# JBC_Station_V3.net
KiCad netlist of a schematic drawn in EAGLE
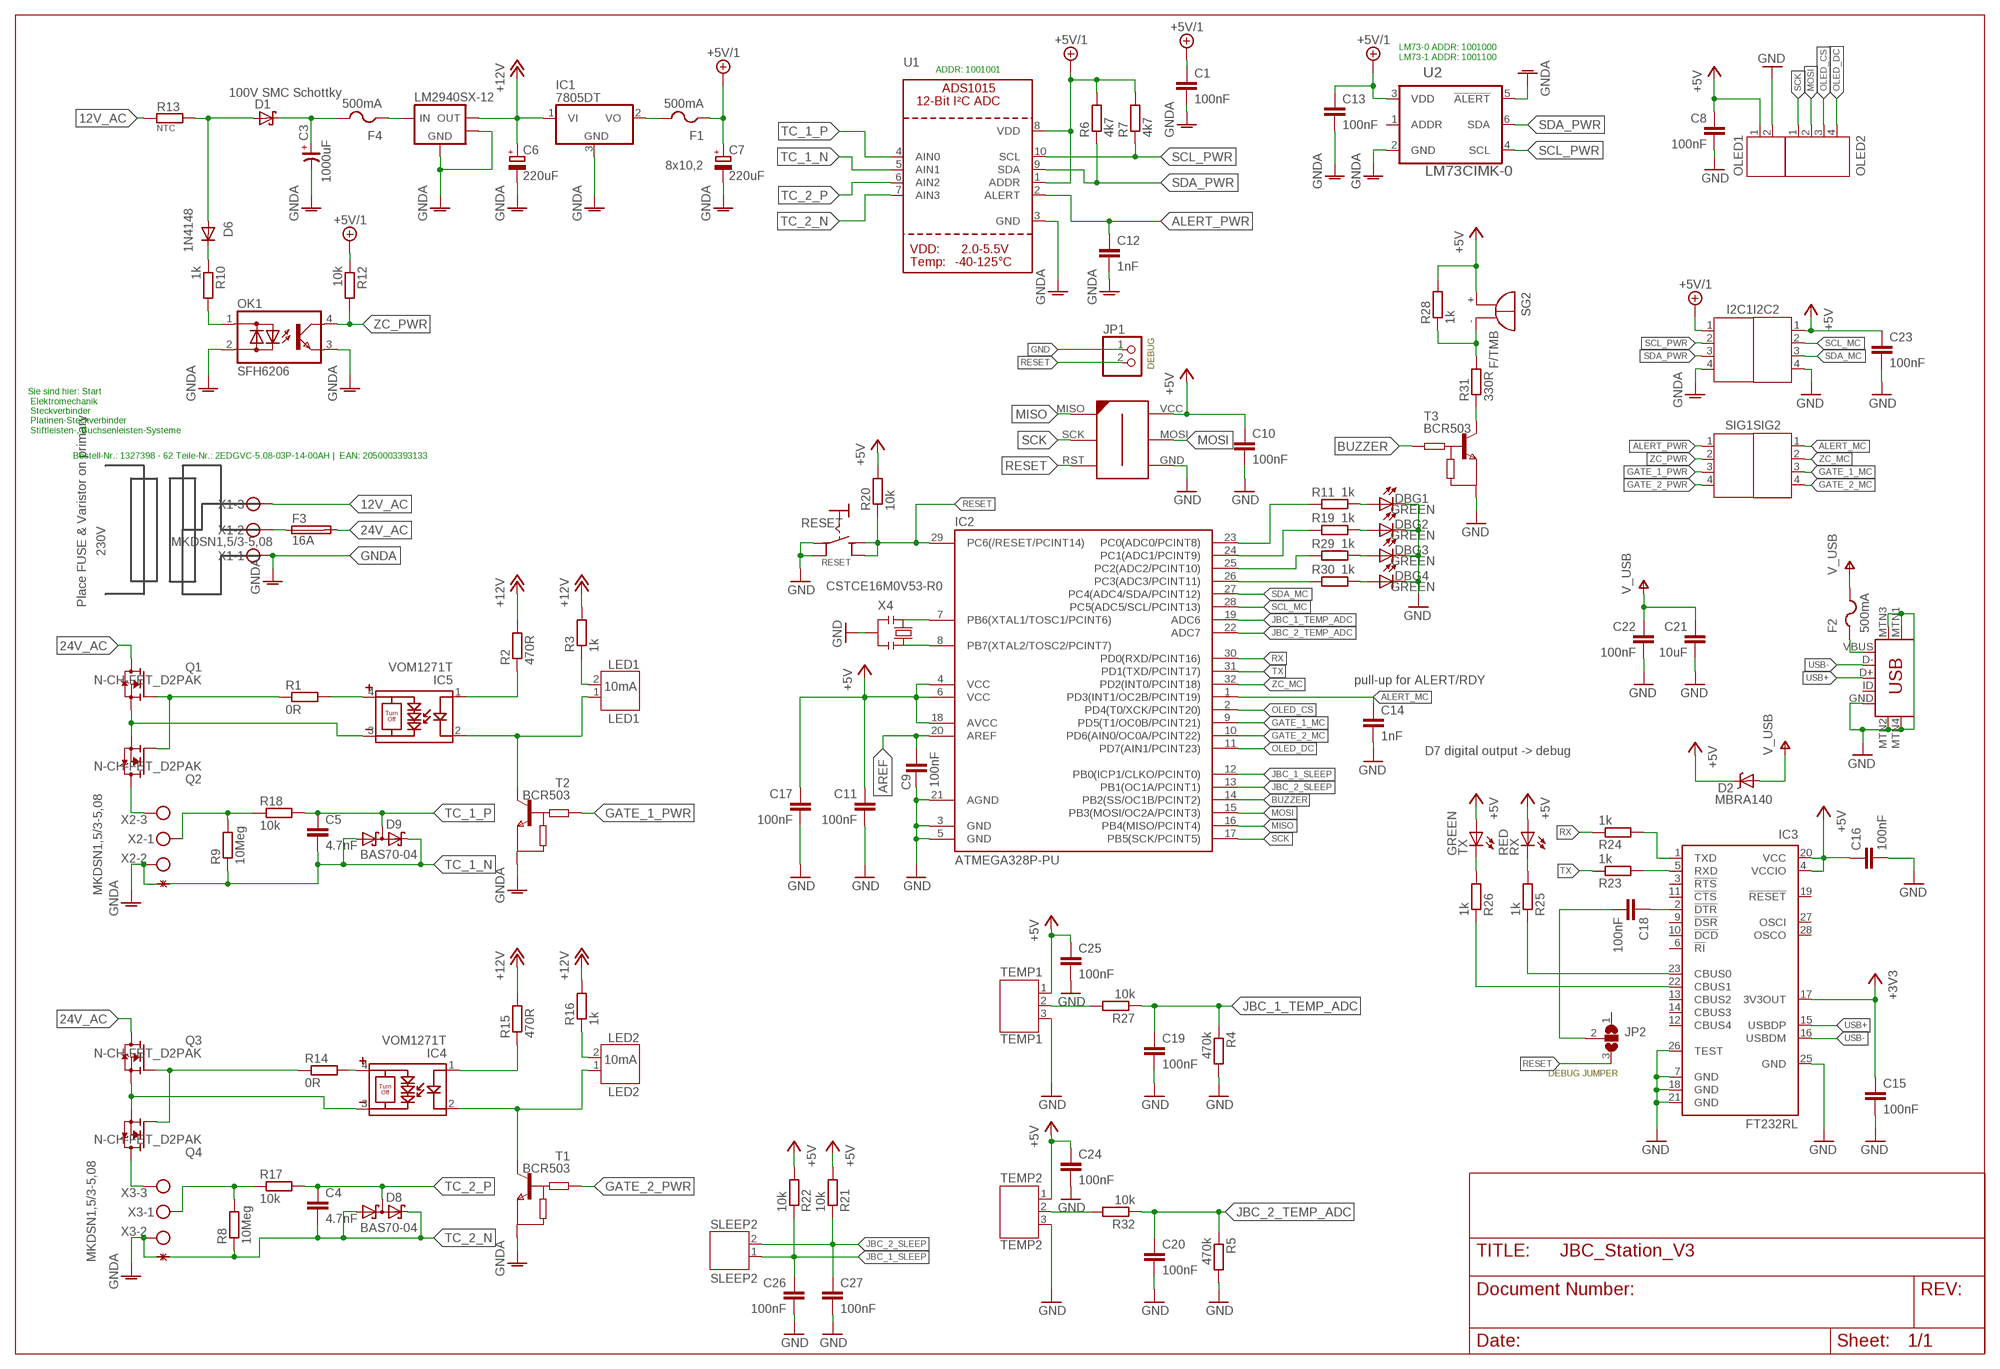
[diagram p0: schematic, sheet 1]

(export (version "E")
  (design (tool "Eeschema 10.0.6"))
  (components
    (comp (ref "C1")
      (value "100nF")
      (footprint "eagle-import:C0805")
      (libsource (lib "eagle-import") (part "C-EUC0805"))
    )
    (comp (ref "C3")
      (value "1000uF")
      (footprint "eagle-import:CSV-H")
      (libsource (lib "eagle-import") (part "CP_SV-H"))
    )
    (comp (ref "C4")
      (value "4.7nF")
      (footprint "eagle-import:C0805")
      (libsource (lib "eagle-import") (part "C-EUC0805"))
    )
    (comp (ref "C5")
      (value "4.7nF")
      (footprint "eagle-import:C0805")
      (libsource (lib "eagle-import") (part "C-EUC0805"))
    )
    (comp (ref "C6")
      (value "220uF")
      (footprint "eagle-import:PANASONIC_E")
      (libsource (lib "eagle-import") (part "CPOL-EUE"))
    )
    (comp (ref "C7")
      (value "220uF")
      (footprint "eagle-import:PANASONIC_E")
      (libsource (lib "eagle-import") (part "CPOL-EUE"))
    )
    (comp (ref "C8")
      (value "100nF")
      (footprint "eagle-import:C0805")
      (libsource (lib "eagle-import") (part "C-EUC0805"))
    )
    (comp (ref "C9")
      (value "100nF")
      (footprint "eagle-import:C0805")
      (libsource (lib "eagle-import") (part "C-EUC0805"))
    )
    (comp (ref "C10")
      (value "100nF")
      (footprint "eagle-import:C0805")
      (libsource (lib "eagle-import") (part "C-EUC0805"))
    )
    (comp (ref "C11")
      (value "100nF")
      (footprint "eagle-import:C0805")
      (libsource (lib "eagle-import") (part "C-EUC0805"))
    )
    (comp (ref "C12")
      (value "1nF")
      (footprint "eagle-import:C0805")
      (libsource (lib "eagle-import") (part "C-EUC0805"))
    )
    (comp (ref "C13")
      (value "100nF")
      (footprint "eagle-import:C0805")
      (libsource (lib "eagle-import") (part "C-EUC0805"))
    )
    (comp (ref "C14")
      (value "1nF")
      (footprint "eagle-import:C0805")
      (libsource (lib "eagle-import") (part "C-EUC0805"))
    )
    (comp (ref "C15")
      (value "100nF")
      (footprint "eagle-import:C0805")
      (libsource (lib "eagle-import") (part "C-EUC0805"))
    )
    (comp (ref "C16")
      (value "100nF")
      (footprint "eagle-import:C0805")
      (libsource (lib "eagle-import") (part "C-EUC0805"))
    )
    (comp (ref "C17")
      (value "100nF")
      (footprint "eagle-import:C0805")
      (libsource (lib "eagle-import") (part "C-EUC0805"))
    )
    (comp (ref "C18")
      (value "100nF")
      (footprint "eagle-import:C0805")
      (libsource (lib "eagle-import") (part "C-EUC0805"))
    )
    (comp (ref "C19")
      (value "100nF")
      (footprint "eagle-import:C0805")
      (libsource (lib "eagle-import") (part "C-EUC0805"))
    )
    (comp (ref "C20")
      (value "100nF")
      (footprint "eagle-import:C0805")
      (libsource (lib "eagle-import") (part "C-EUC0805"))
    )
    (comp (ref "C21")
      (value "10uF")
      (footprint "eagle-import:C1210")
      (libsource (lib "eagle-import") (part "C-EUC1210"))
    )
    (comp (ref "C22")
      (value "100nF")
      (footprint "eagle-import:C0805")
      (libsource (lib "eagle-import") (part "C-EUC0805"))
    )
    (comp (ref "C23")
      (value "100nF")
      (footprint "eagle-import:C0805")
      (libsource (lib "eagle-import") (part "C-EUC0805"))
    )
    (comp (ref "C24")
      (value "100nF")
      (footprint "eagle-import:C0805")
      (libsource (lib "eagle-import") (part "C-EUC0805"))
    )
    (comp (ref "C25")
      (value "100nF")
      (footprint "eagle-import:C0805")
      (libsource (lib "eagle-import") (part "C-EUC0805"))
    )
    (comp (ref "C26")
      (value "100nF")
      (footprint "eagle-import:C0805")
      (libsource (lib "eagle-import") (part "C-EUC0805"))
    )
    (comp (ref "C27")
      (value "100nF")
      (footprint "eagle-import:C0805")
      (libsource (lib "eagle-import") (part "C-EUC0805"))
    )
    (comp (ref "D1")
      (value "100V SMC Schottky")
      (footprint "eagle-import:SMC")
      (libsource (lib "eagle-import") (part "SCHOTTKY-DIODESMC"))
    )
    (comp (ref "D2")
      (value "MBRA140")
      (footprint "eagle-import:SMA-DIODE")
      (libsource (lib "eagle-import") (part "DIODE-SCHOTTKY_"))
    )
    (comp (ref "D6")
      (value "1N4148")
      (footprint "eagle-import:MINIMELF")
      (libsource (lib "eagle-import") (part "DIODE-MINIMELF"))
    )
    (comp (ref "D8")
      (value "BAS70-04")
      (footprint "eagle-import:SOT23")
      (libsource (lib "eagle-import") (part "BAS70-04"))
    )
    (comp (ref "D9")
      (value "BAS70-04")
      (footprint "eagle-import:SOT23")
      (libsource (lib "eagle-import") (part "BAS70-04"))
    )
    (comp (ref "DBG1")
      (value "GREEN")
      (footprint "eagle-import:CHIP-LED0603")
      (libsource (lib "eagle-import") (part "LEDCHIP-LED0603"))
    )
    (comp (ref "DBG2")
      (value "GREEN")
      (footprint "eagle-import:CHIP-LED0603")
      (libsource (lib "eagle-import") (part "LEDCHIP-LED0603"))
    )
    (comp (ref "DBG3")
      (value "GREEN")
      (footprint "eagle-import:CHIP-LED0603")
      (libsource (lib "eagle-import") (part "LEDCHIP-LED0603"))
    )
    (comp (ref "DBG4")
      (value "GREEN")
      (footprint "eagle-import:CHIP-LED0603")
      (libsource (lib "eagle-import") (part "LEDCHIP-LED0603"))
    )
    (comp (ref "F1")
      (value "500mA")
      (footprint "eagle-import:R1206")
      (libsource (lib "eagle-import") (part "PTCFUSE-1206"))
    )
    (comp (ref "F2")
      (value "500mA")
      (footprint "eagle-import:R1206")
      (libsource (lib "eagle-import") (part "PTCFUSE-1206"))
    )
    (comp (ref "F3")
      (value "16A")
      (footprint "eagle-import:SH25")
      (fields (field (name "MF") "SCHURTER") (field (name "MPN") "0031.8211"))
      (libsource (lib "eagle-import") (part "SH25"))
    )
    (comp (ref "F4")
      (value "500mA")
      (footprint "eagle-import:R1206")
      (libsource (lib "eagle-import") (part "PTCFUSE-1206"))
    )
    (comp (ref "I2C1")
      (value "JST-PH4")
      (footprint "eagle-import:JST-PH4")
      (libsource (lib "eagle-import") (part "JST-PH4"))
    )
    (comp (ref "I2C2")
      (value "JST-PH4")
      (footprint "eagle-import:JST-PH4")
      (libsource (lib "eagle-import") (part "JST-PH4"))
    )
    (comp (ref "IC1")
      (value "7805DT")
      (footprint "eagle-import:TO252")
      (libsource (lib "eagle-import") (part "78DT05"))
    )
    (comp (ref "IC2")
      (value "ATMEGA328P-PU")
      (footprint "eagle-import:TQFP32-08")
      (libsource (lib "eagle-import") (part "MEGA48/88/168-AU"))
    )
    (comp (ref "IC3")
      (value "FT232RL")
      (footprint "eagle-import:SSOP28")
      (libsource (lib "eagle-import") (part "FT232RL"))
    )
    (comp (ref "IC4")
      (value "VOM1271T")
      (footprint "eagle-import:SOP-4")
      (libsource (lib "eagle-import") (part "VOM1271T"))
    )
    (comp (ref "IC5")
      (value "VOM1271T")
      (footprint "eagle-import:SOP-4")
      (libsource (lib "eagle-import") (part "VOM1271T"))
    )
    (comp (ref "JP1")
      (value "PINHD-1X2_2.54")
      (footprint "eagle-import:1X02")
      (libsource (lib "eagle-import") (part "PINHD-1X2_2.54"))
    )
    (comp (ref "JP2")
      (value "SJ2W")
      (footprint "eagle-import:SJ_2")
      (libsource (lib "eagle-import") (part "SJ2W"))
    )
    (comp (ref "LED1")
      (value "LED1")
      (footprint "eagle-import:JST-PH2")
      (libsource (lib "eagle-import") (part "JST-PH2"))
    )
    (comp (ref "LED2")
      (value "LED2")
      (footprint "eagle-import:JST-PH2")
      (libsource (lib "eagle-import") (part "JST-PH2"))
    )
    (comp (ref "LM2940SX-12")
      (value "LM2940KTT")
      (footprint "eagle-import:TO263-3")
      (libsource (lib "eagle-import") (part "LM2940KTT"))
    )
    (comp (ref "OK1")
      (value "SFH6206")
      (footprint "eagle-import:DIL4-SMD")
      (fields (field (name "MF") "VISHAY/TELEFUNKEN") (field (name "MPN") "SFH6206-3"))
      (libsource (lib "eagle-import") (part "SFH6206"))
    )
    (comp (ref "OLED1")
      (value "JST-PH2")
      (footprint "eagle-import:JST-PH2")
      (libsource (lib "eagle-import") (part "JST-PH2"))
    )
    (comp (ref "OLED2")
      (value "JST-PH4")
      (footprint "eagle-import:JST-PH4")
      (libsource (lib "eagle-import") (part "JST-PH4"))
    )
    (comp (ref "Q1")
      (value "N-CH-FET_D2PAK")
      (footprint "eagle-import:D2PACK")
      (libsource (lib "eagle-import") (part "N-CH-FET_D2PAK"))
    )
    (comp (ref "Q2")
      (value "N-CH-FET_D2PAK")
      (footprint "eagle-import:D2PACK")
      (libsource (lib "eagle-import") (part "N-CH-FET_D2PAK"))
    )
    (comp (ref "Q3")
      (value "N-CH-FET_D2PAK")
      (footprint "eagle-import:D2PACK")
      (libsource (lib "eagle-import") (part "N-CH-FET_D2PAK"))
    )
    (comp (ref "Q4")
      (value "N-CH-FET_D2PAK")
      (footprint "eagle-import:D2PACK")
      (libsource (lib "eagle-import") (part "N-CH-FET_D2PAK"))
    )
    (comp (ref "R1")
      (value "0R")
      (footprint "eagle-import:R0805")
      (libsource (lib "eagle-import") (part "R-EU_R0805"))
    )
    (comp (ref "R2")
      (value "470R")
      (footprint "eagle-import:R0805")
      (libsource (lib "eagle-import") (part "R-EU_R0805"))
    )
    (comp (ref "R3")
      (value "1k")
      (footprint "eagle-import:R0805")
      (libsource (lib "eagle-import") (part "R-EU_R0805"))
    )
    (comp (ref "R4")
      (value "470k")
      (footprint "eagle-import:R0805")
      (libsource (lib "eagle-import") (part "R-EU_R0805"))
    )
    (comp (ref "R5")
      (value "470k")
      (footprint "eagle-import:R0805")
      (libsource (lib "eagle-import") (part "R-EU_R0805"))
    )
    (comp (ref "R6")
      (value "4k7")
      (footprint "eagle-import:R0805")
      (libsource (lib "eagle-import") (part "R-EU_R0805"))
    )
    (comp (ref "R7")
      (value "4k7")
      (footprint "eagle-import:R0805")
      (libsource (lib "eagle-import") (part "R-EU_R0805"))
    )
    (comp (ref "R8")
      (value "10Meg")
      (footprint "eagle-import:R0805")
      (libsource (lib "eagle-import") (part "R-EU_R0805"))
    )
    (comp (ref "R9")
      (value "10Meg")
      (footprint "eagle-import:R0805")
      (libsource (lib "eagle-import") (part "R-EU_R0805"))
    )
    (comp (ref "R10")
      (value "1k")
      (footprint "eagle-import:R0805")
      (libsource (lib "eagle-import") (part "R-EU_R0805"))
    )
    (comp (ref "R11")
      (value "1k")
      (footprint "eagle-import:R0805")
      (libsource (lib "eagle-import") (part "R-EU_R0805"))
    )
    (comp (ref "R12")
      (value "10k")
      (footprint "eagle-import:R0805")
      (libsource (lib "eagle-import") (part "R-EU_R0805"))
    )
    (comp (ref "R13")
      (value "NTC")
      (footprint "eagle-import:SQM-VERTICAL-7W")
      (libsource (lib "eagle-import") (part "SQMR7"))
    )
    (comp (ref "R14")
      (value "0R")
      (footprint "eagle-import:R0805")
      (libsource (lib "eagle-import") (part "R-EU_R0805"))
    )
    (comp (ref "R15")
      (value "470R")
      (footprint "eagle-import:R0805")
      (libsource (lib "eagle-import") (part "R-EU_R0805"))
    )
    (comp (ref "R16")
      (value "1k")
      (footprint "eagle-import:R0805")
      (libsource (lib "eagle-import") (part "R-EU_R0805"))
    )
    (comp (ref "R17")
      (value "10k")
      (footprint "eagle-import:R0805")
      (libsource (lib "eagle-import") (part "R-EU_R0805"))
    )
    (comp (ref "R18")
      (value "10k")
      (footprint "eagle-import:R0805")
      (libsource (lib "eagle-import") (part "R-EU_R0805"))
    )
    (comp (ref "R19")
      (value "1k")
      (footprint "eagle-import:R0805")
      (libsource (lib "eagle-import") (part "R-EU_R0805"))
    )
    (comp (ref "R20")
      (value "10k")
      (footprint "eagle-import:R0805")
      (libsource (lib "eagle-import") (part "R-EU_R0805"))
    )
    (comp (ref "R21")
      (value "10k")
      (footprint "eagle-import:R0805")
      (libsource (lib "eagle-import") (part "R-EU_R0805"))
    )
    (comp (ref "R22")
      (value "10k")
      (footprint "eagle-import:R0805")
      (libsource (lib "eagle-import") (part "R-EU_R0805"))
    )
    (comp (ref "R23")
      (value "1k")
      (footprint "eagle-import:R0805")
      (libsource (lib "eagle-import") (part "R-EU_R0805"))
    )
    (comp (ref "R24")
      (value "1k")
      (footprint "eagle-import:R0805")
      (libsource (lib "eagle-import") (part "R-EU_R0805"))
    )
    (comp (ref "R25")
      (value "1k")
      (footprint "eagle-import:R0805")
      (libsource (lib "eagle-import") (part "R-EU_R0805"))
    )
    (comp (ref "R26")
      (value "1k")
      (footprint "eagle-import:R0805")
      (libsource (lib "eagle-import") (part "R-EU_R0805"))
    )
    (comp (ref "R27")
      (value "10k")
      (footprint "eagle-import:R0805")
      (libsource (lib "eagle-import") (part "R-EU_R0805"))
    )
    (comp (ref "R28")
      (value "1k")
      (footprint "eagle-import:R0805")
      (libsource (lib "eagle-import") (part "R-EU_R0805"))
    )
    (comp (ref "R29")
      (value "1k")
      (footprint "eagle-import:R0805")
      (libsource (lib "eagle-import") (part "R-EU_R0805"))
    )
    (comp (ref "R30")
      (value "1k")
      (footprint "eagle-import:R0805")
      (libsource (lib "eagle-import") (part "R-EU_R0805"))
    )
    (comp (ref "R31")
      (value "330R")
      (footprint "eagle-import:R0805")
      (libsource (lib "eagle-import") (part "R-EU_R0805"))
    )
    (comp (ref "R32")
      (value "10k")
      (footprint "eagle-import:R0805")
      (libsource (lib "eagle-import") (part "R-EU_R0805"))
    )
    (comp (ref "RESET")
      (value "RESET")
      (footprint "eagle-import:TASTE_DRST_TA1")
      (libsource (lib "eagle-import") (part "TASTE_DRST_TA1"))
    )
    (comp (ref "RX")
      (value "RED")
      (footprint "eagle-import:CHIP-LED0603")
      (libsource (lib "eagle-import") (part "LEDCHIP-LED0603"))
    )
    (comp (ref "SG2")
      (value "F/TMB")
      (footprint "eagle-import:F_TMB")
      (libsource (lib "eagle-import") (part "F/TMB"))
    )
    (comp (ref "SIG1")
      (value "JST-PH4")
      (footprint "eagle-import:JST-PH4")
      (libsource (lib "eagle-import") (part "JST-PH4"))
    )
    (comp (ref "SIG2")
      (value "JST-PH4")
      (footprint "eagle-import:JST-PH4")
      (libsource (lib "eagle-import") (part "JST-PH4"))
    )
    (comp (ref "SLEEP2")
      (value "SLEEP2")
      (footprint "eagle-import:JST-PH2")
      (libsource (lib "eagle-import") (part "JST-PH2"))
    )
    (comp (ref "T1")
      (value "BCR503")
      (footprint "eagle-import:GM4_BIP_SOT23_RZ")
      (libsource (lib "eagle-import") (part "GM4_BIP_NPN-DIG_SOT23_RZ"))
    )
    (comp (ref "T2")
      (value "BCR503")
      (footprint "eagle-import:GM4_BIP_SOT23_RZ")
      (libsource (lib "eagle-import") (part "GM4_BIP_NPN-DIG_SOT23_RZ"))
    )
    (comp (ref "T3")
      (value "BCR503")
      (footprint "eagle-import:GM4_BIP_SOT23_RZ")
      (libsource (lib "eagle-import") (part "GM4_BIP_NPN-DIG_SOT23_RZ"))
    )
    (comp (ref "TEMP1")
      (value "TEMP1")
      (footprint "eagle-import:JST-PH3")
      (libsource (lib "eagle-import") (part "JST-PH3"))
    )
    (comp (ref "TEMP2")
      (value "TEMP2")
      (footprint "eagle-import:JST-PH3")
      (libsource (lib "eagle-import") (part "JST-PH3"))
    )
    (comp (ref "TX")
      (value "GREEN")
      (footprint "eagle-import:CHIP-LED0603")
      (libsource (lib "eagle-import") (part "LEDCHIP-LED0603"))
    )
    (comp (ref "U$2")
      (value "STARPONT")
      (footprint "eagle-import:STARPOINT")
      (libsource (lib "eagle-import") (part "STARPONT"))
    )
    (comp (ref "U$3")
      (value "STARPONT")
      (footprint "eagle-import:STARPOINT")
      (libsource (lib "eagle-import") (part "STARPONT"))
    )
    (comp (ref "U$5")
      (value "AVR-ISP-6-EDGE")
      (footprint "eagle-import:6PAD_ISP")
      (libsource (lib "eagle-import") (part "AVR-ISP-6-EDGE"))
    )
    (comp (ref "U1")
      (value "ADC_ADS1015")
      (footprint "eagle-import:MSOP10")
      (libsource (lib "eagle-import") (part "ADC_ADS1015"))
    )
    (comp (ref "U2")
      (value "LM73CIMK-0")
      (footprint "eagle-import:SOT95P285X100-6N")
      (libsource (lib "eagle-import") (part "LM73CIMK-0"))
    )
    (comp (ref "USB")
      (value "USB-MINIB-5PIN")
      (footprint "eagle-import:USB-MINIB")
      (libsource (lib "eagle-import") (part "USB-MINIB-5PIN"))
    )
    (comp (ref "X1")
      (value "MKDSN1,5/3-5,08")
      (footprint "eagle-import:MKDSN1,5_3-5,08")
      (libsource (lib "eagle-import") (part "MKDSN1,5/3-5,08"))
    )
    (comp (ref "X2")
      (value "MKDSN1,5/3-5,08")
      (footprint "eagle-import:MKDSN1,5_3-5,08")
      (libsource (lib "eagle-import") (part "MKDSN1,5/3-5,08"))
    )
    (comp (ref "X3")
      (value "MKDSN1,5/3-5,08")
      (footprint "eagle-import:MKDSN1,5_3-5,08")
      (libsource (lib "eagle-import") (part "MKDSN1,5/3-5,08"))
    )
    (comp (ref "X4")
      (value "CSTCE16M0V53-R0")
      (footprint "eagle-import:RESONATOR")
      (libsource (lib "eagle-import") (part "0011_CSTCE16M0V53-R0"))
    )
  )
  (nets
    (net (code "1") (name "+3V3") (class "Default")
      (node (ref "C15") (pin "1") (pinfunction "1_1") (pintype "passive"))
      (node (ref "IC3") (pin "17") (pinfunction "3V3OUT_17") (pintype "output"))
    )
    (net (code "2") (name "+5V") (class "Default")
      (node (ref "C10") (pin "1") (pinfunction "1_1") (pintype "passive"))
      (node (ref "C11") (pin "1") (pinfunction "1_1") (pintype "passive"))
      (node (ref "C16") (pin "1") (pinfunction "1_1") (pintype "passive"))
      (node (ref "C17") (pin "1") (pinfunction "1_1") (pintype "passive"))
      (node (ref "C23") (pin "1") (pinfunction "1_1") (pintype "passive"))
      (node (ref "C24") (pin "1") (pinfunction "1_1") (pintype "passive"))
      (node (ref "C25") (pin "1") (pinfunction "1_1") (pintype "passive"))
      (node (ref "C8") (pin "1") (pinfunction "1_1") (pintype "passive"))
      (node (ref "D2") (pin "C") (pinfunction "C_C") (pintype "passive"))
      (node (ref "I2C2") (pin "1") (pinfunction "1_1") (pintype "passive"))
      (node (ref "IC2") (pin "18") (pinfunction "AVCC_18") (pintype "passive"))
      (node (ref "IC2") (pin "4") (pinfunction "VCC_4") (pintype "power_in"))
      (node (ref "IC2") (pin "6") (pinfunction "VCC_6") (pintype "power_in"))
      (node (ref "IC3") (pin "20") (pinfunction "VCC_20") (pintype "power_in"))
      (node (ref "IC3") (pin "4") (pinfunction "VCCIO_4") (pintype "power_in"))
      (node (ref "OLED1") (pin "1") (pinfunction "1_1") (pintype "passive"))
      (node (ref "R20") (pin "2") (pinfunction "2_2") (pintype "passive"))
      (node (ref "R21") (pin "2") (pinfunction "2_2") (pintype "passive"))
      (node (ref "R22") (pin "2") (pinfunction "2_2") (pintype "passive"))
      (node (ref "R28") (pin "2") (pinfunction "2_2") (pintype "passive"))
      (node (ref "RX") (pin "A") (pinfunction "A_A") (pintype "passive"))
      (node (ref "SG2") (pin "+") (pinfunction "+_+") (pintype "passive"))
      (node (ref "TEMP1") (pin "1") (pinfunction "1_1") (pintype "passive"))
      (node (ref "TEMP2") (pin "1") (pinfunction "1_1") (pintype "passive"))
      (node (ref "TX") (pin "A") (pinfunction "A_A") (pintype "passive"))
      (node (ref "U$5") (pin "VCC") (pinfunction "P$6_VCC") (pintype "bidirectional"))
    )
    (net (code "3") (name "+5V{slash}1") (class "Default")
      (node (ref "C1") (pin "1") (pinfunction "1_1") (pintype "passive"))
      (node (ref "C13") (pin "1") (pinfunction "1_1") (pintype "passive"))
      (node (ref "C7") (pin "+") (pinfunction "+_+") (pintype "passive"))
      (node (ref "F1") (pin "1") (pinfunction "1_1") (pintype "passive"))
      (node (ref "I2C1") (pin "1") (pinfunction "1_1") (pintype "passive"))
      (node (ref "R12") (pin "1") (pinfunction "1_1") (pintype "passive"))
      (node (ref "R6") (pin "2") (pinfunction "2_2") (pintype "passive"))
      (node (ref "R7") (pin "2") (pinfunction "2_2") (pintype "passive"))
      (node (ref "U1") (pin "1") (pinfunction "ADDR_1") (pintype "bidirectional"))
      (node (ref "U1") (pin "8") (pinfunction "VDD_8") (pintype "bidirectional"))
      (node (ref "U2") (pin "3") (pinfunction "VDD_3") (pintype "power_in"))
    )
    (net (code "4") (name "+12V") (class "Default")
      (node (ref "C6") (pin "+") (pinfunction "+_+") (pintype "passive"))
      (node (ref "IC1") (pin "1") (pinfunction "VI_1") (pintype "input"))
      (node (ref "LM2940SX-12") (pin "3") (pinfunction "VOUT_3") (pintype "power_in"))
      (node (ref "R15") (pin "2") (pinfunction "2_2") (pintype "passive"))
      (node (ref "R16") (pin "2") (pinfunction "2_2") (pintype "passive"))
      (node (ref "R2") (pin "2") (pinfunction "2_2") (pintype "passive"))
      (node (ref "R3") (pin "2") (pinfunction "2_2") (pintype "passive"))
    )
    (net (code "5") (name "12V_AC") (class "Default")
      (node (ref "R13") (pin "P$1") (pinfunction "1_P$1") (pintype "passive"))
      (node (ref "X1") (pin "3") (pinfunction "KL_3") (pintype "passive"))
    )
    (net (code "6") (name "24V_AC") (class "Default")
      (node (ref "F3") (pin "2") (pinfunction "2_2") (pintype "passive"))
      (node (ref "Q1") (pin "2") (pinfunction "D_2") (pintype "passive"))
      (node (ref "Q3") (pin "2") (pinfunction "D_2") (pintype "passive"))
    )
    (net (code "7") (name "ALERT_MC") (class "Default")
      (node (ref "C14") (pin "1") (pinfunction "1_1") (pintype "passive"))
      (node (ref "IC2") (pin "1") (pinfunction "PD3(INT1/OC2B/PCINT19)_1") (pintype "bidirectional"))
      (node (ref "SIG2") (pin "1") (pinfunction "1_1") (pintype "passive"))
    )
    (net (code "8") (name "ALERT_PWR") (class "Default")
      (node (ref "C12") (pin "1") (pinfunction "1_1") (pintype "passive"))
      (node (ref "SIG1") (pin "1") (pinfunction "1_1") (pintype "passive"))
      (node (ref "U1") (pin "2") (pinfunction "ALERT_2") (pintype "bidirectional"))
    )
    (net (code "9") (name "AREF") (class "Default")
      (node (ref "C9") (pin "1") (pinfunction "1_1") (pintype "passive"))
      (node (ref "IC2") (pin "20") (pinfunction "AREF_20") (pintype "passive"))
    )
    (net (code "10") (name "BUZZER") (class "Default")
      (node (ref "IC2") (pin "14") (pinfunction "PB2(SS/OC1B/PCINT2)_14") (pintype "bidirectional"))
      (node (ref "T3") (pin "1") (pinfunction "B_1") (pintype "passive"))
    )
    (net (code "11") (name "GATE_1_MC") (class "Default")
      (node (ref "IC2") (pin "9") (pinfunction "PD5(T1/OC0B/PCINT21)_9") (pintype "bidirectional"))
      (node (ref "SIG2") (pin "3") (pinfunction "3_3") (pintype "passive"))
    )
    (net (code "12") (name "GATE_1_PWR") (class "Default")
      (node (ref "SIG1") (pin "3") (pinfunction "3_3") (pintype "passive"))
      (node (ref "T2") (pin "1") (pinfunction "B_1") (pintype "passive"))
    )
    (net (code "13") (name "GATE_2_MC") (class "Default")
      (node (ref "IC2") (pin "10") (pinfunction "PD6(AIN0/OC0A/PCINT22)_10") (pintype "bidirectional"))
      (node (ref "SIG2") (pin "4") (pinfunction "4_4") (pintype "passive"))
    )
    (net (code "14") (name "GATE_2_PWR") (class "Default")
      (node (ref "SIG1") (pin "4") (pinfunction "4_4") (pintype "passive"))
      (node (ref "T1") (pin "1") (pinfunction "B_1") (pintype "passive"))
    )
    (net (code "15") (name "GND") (class "Default")
      (node (ref "C10") (pin "2") (pinfunction "2_2") (pintype "passive"))
      (node (ref "C11") (pin "2") (pinfunction "2_2") (pintype "passive"))
      (node (ref "C14") (pin "2") (pinfunction "2_2") (pintype "passive"))
      (node (ref "C15") (pin "2") (pinfunction "2_2") (pintype "passive"))
      (node (ref "C16") (pin "2") (pinfunction "2_2") (pintype "passive"))
      (node (ref "C17") (pin "2") (pinfunction "2_2") (pintype "passive"))
      (node (ref "C19") (pin "2") (pinfunction "2_2") (pintype "passive"))
      (node (ref "C20") (pin "2") (pinfunction "2_2") (pintype "passive"))
      (node (ref "C21") (pin "2") (pinfunction "2_2") (pintype "passive"))
      (node (ref "C22") (pin "2") (pinfunction "2_2") (pintype "passive"))
      (node (ref "C23") (pin "2") (pinfunction "2_2") (pintype "passive"))
      (node (ref "C24") (pin "2") (pinfunction "2_2") (pintype "passive"))
      (node (ref "C25") (pin "2") (pinfunction "2_2") (pintype "passive"))
      (node (ref "C26") (pin "2") (pinfunction "2_2") (pintype "passive"))
      (node (ref "C27") (pin "2") (pinfunction "2_2") (pintype "passive"))
      (node (ref "C8") (pin "2") (pinfunction "2_2") (pintype "passive"))
      (node (ref "C9") (pin "2") (pinfunction "2_2") (pintype "passive"))
      (node (ref "DBG1") (pin "C") (pinfunction "C_C") (pintype "passive"))
      (node (ref "DBG2") (pin "C") (pinfunction "C_C") (pintype "passive"))
      (node (ref "DBG3") (pin "C") (pinfunction "C_C") (pintype "passive"))
      (node (ref "DBG4") (pin "C") (pinfunction "C_C") (pintype "passive"))
      (node (ref "I2C2") (pin "4") (pinfunction "4_4") (pintype "passive"))
      (node (ref "IC2") (pin "21") (pinfunction "AGND_21") (pintype "power_in"))
      (node (ref "IC2") (pin "3") (pinfunction "GND_3") (pintype "power_in"))
      (node (ref "IC2") (pin "5") (pinfunction "GND_5") (pintype "power_in"))
      (node (ref "IC3") (pin "18") (pinfunction "GND_18") (pintype "power_in"))
      (node (ref "IC3") (pin "21") (pinfunction "GND_21") (pintype "power_in"))
      (node (ref "IC3") (pin "25") (pinfunction "GND_25") (pintype "power_in"))
      (node (ref "IC3") (pin "26") (pinfunction "TEST_26") (pintype "input"))
      (node (ref "IC3") (pin "7") (pinfunction "GND_7") (pintype "power_in"))
      (node (ref "JP1") (pin "1") (pinfunction "1_1") (pintype "passive"))
      (node (ref "OLED1") (pin "2") (pinfunction "2_2") (pintype "passive"))
      (node (ref "R4") (pin "2") (pinfunction "2_2") (pintype "passive"))
      (node (ref "R5") (pin "2") (pinfunction "2_2") (pintype "passive"))
      (node (ref "RESET") (pin "P$1") (pinfunction "1_P$1") (pintype "passive"))
      (node (ref "RESET") (pin "P$2") (pinfunction "1_P$2") (pintype "passive"))
      (node (ref "T3") (pin "2") (pinfunction "E_2") (pintype "passive"))
      (node (ref "TEMP1") (pin "3") (pinfunction "3_3") (pintype "passive"))
      (node (ref "TEMP2") (pin "3") (pinfunction "3_3") (pintype "passive"))
      (node (ref "U$5") (pin "GND") (pinfunction "P$4_GND") (pintype "bidirectional"))
      (node (ref "USB") (pin "GND") (pinfunction "GND_GND") (pintype "bidirectional"))
      (node (ref "USB") (pin "MTN1") (pinfunction "MTN2_MTN1") (pintype "bidirectional"))
      (node (ref "USB") (pin "MTN2") (pinfunction "MTN3_MTN2") (pintype "bidirectional"))
      (node (ref "USB") (pin "MTN3") (pinfunction "MTN1_MTN3") (pintype "bidirectional"))
      (node (ref "USB") (pin "MTN4") (pinfunction "MTN4_MTN4") (pintype "bidirectional"))
      (node (ref "X4") (pin "2") (pinfunction "2_2") (pintype "passive"))
    )
    (net (code "16") (name "GNDA") (class "Default")
      (node (ref "C1") (pin "2") (pinfunction "2_2") (pintype "passive"))
      (node (ref "C12") (pin "2") (pinfunction "2_2") (pintype "passive"))
      (node (ref "C13") (pin "2") (pinfunction "2_2") (pintype "passive"))
      (node (ref "C3") (pin "-") (pinfunction "-_-") (pintype "passive"))
      (node (ref "C6") (pin "-") (pinfunction "-_-") (pintype "passive"))
      (node (ref "C7") (pin "-") (pinfunction "-_-") (pintype "passive"))
      (node (ref "I2C1") (pin "4") (pinfunction "4_4") (pintype "passive"))
      (node (ref "IC1") (pin "3") (pinfunction "GND_3") (pintype "passive"))
      (node (ref "LM2940SX-12") (pin "2") (pinfunction "GND_2") (pintype "power_in"))
      (node (ref "LM2940SX-12") (pin "TAB") (pinfunction "TAB_TAB") (pintype "power_in"))
      (node (ref "OK1") (pin "2") (pinfunction "AC2_2") (pintype "passive"))
      (node (ref "OK1") (pin "3") (pinfunction "E_3") (pintype "passive"))
      (node (ref "T1") (pin "2") (pinfunction "E_2") (pintype "passive"))
      (node (ref "T2") (pin "2") (pinfunction "E_2") (pintype "passive"))
      (node (ref "U$2") (pin "P$2") (pinfunction "P$2_P$2") (pintype "bidirectional"))
      (node (ref "U$3") (pin "P$2") (pinfunction "P$2_P$2") (pintype "bidirectional"))
      (node (ref "U1") (pin "3") (pinfunction "GND_3") (pintype "bidirectional"))
      (node (ref "U2") (pin "2") (pinfunction "GND_2") (pintype "passive"))
      (node (ref "U2") (pin "5") (pinfunction "~{ALERT}_5") (pintype "output"))
      (node (ref "X1") (pin "1") (pinfunction "KL_1") (pintype "passive"))
      (node (ref "X2") (pin "2") (pinfunction "KL_2") (pintype "passive"))
      (node (ref "X3") (pin "2") (pinfunction "KL_2") (pintype "passive"))
    )
    (net (code "17") (name "JBC_1_SLEEP") (class "Default")
      (node (ref "C26") (pin "1") (pinfunction "1_1") (pintype "passive"))
      (node (ref "IC2") (pin "12") (pinfunction "PB0(ICP1/CLKO/PCINT0)_12") (pintype "bidirectional"))
      (node (ref "R22") (pin "1") (pinfunction "1_1") (pintype "passive"))
      (node (ref "SLEEP2") (pin "1") (pinfunction "1_1") (pintype "passive"))
    )
    (net (code "18") (name "JBC_1_TEMP_ADC") (class "Default")
      (node (ref "C19") (pin "1") (pinfunction "1_1") (pintype "passive"))
      (node (ref "IC2") (pin "19") (pinfunction "ADC6_19") (pintype "passive"))
      (node (ref "R27") (pin "1") (pinfunction "1_1") (pintype "passive"))
      (node (ref "R4") (pin "1") (pinfunction "1_1") (pintype "passive"))
    )
    (net (code "19") (name "JBC_2_SLEEP") (class "Default")
      (node (ref "C27") (pin "1") (pinfunction "1_1") (pintype "passive"))
      (node (ref "IC2") (pin "13") (pinfunction "PB1(OC1A/PCINT1)_13") (pintype "bidirectional"))
      (node (ref "R21") (pin "1") (pinfunction "1_1") (pintype "passive"))
      (node (ref "SLEEP2") (pin "2") (pinfunction "2_2") (pintype "passive"))
    )
    (net (code "20") (name "JBC_2_TEMP_ADC") (class "Default")
      (node (ref "C20") (pin "1") (pinfunction "1_1") (pintype "passive"))
      (node (ref "IC2") (pin "22") (pinfunction "ADC7_22") (pintype "passive"))
      (node (ref "R32") (pin "1") (pinfunction "1_1") (pintype "passive"))
      (node (ref "R5") (pin "1") (pinfunction "1_1") (pintype "passive"))
    )
    (net (code "21") (name "MISO") (class "Default")
      (node (ref "IC2") (pin "16") (pinfunction "PB4(MISO/PCINT4)_16") (pintype "bidirectional"))
      (node (ref "U$5") (pin "MISO") (pinfunction "P$1_MISO") (pintype "bidirectional"))
    )
    (net (code "22") (name "MOSI") (class "Default")
      (node (ref "IC2") (pin "15") (pinfunction "PB3(MOSI/OC2A/PCINT3)_15") (pintype "bidirectional"))
      (node (ref "OLED2") (pin "2") (pinfunction "2_2") (pintype "passive"))
      (node (ref "U$5") (pin "MOSI") (pinfunction "P$5_MOSI") (pintype "bidirectional"))
    )
    (net (code "23") (name "Net-(C3-Pad+)") (class "Default")
      (node (ref "C3") (pin "+") (pinfunction "+_+") (pintype "passive"))
      (node (ref "D1") (pin "C") (pinfunction "C_C") (pintype "passive"))
      (node (ref "F4") (pin "2") (pinfunction "2_2") (pintype "passive"))
    )
    (net (code "24") (name "Net-(C18-Pad2)") (class "Default")
      (node (ref "C18") (pin "2") (pinfunction "2_2") (pintype "passive"))
      (node (ref "JP2") (pin "2") (pinfunction "2_2") (pintype "passive"))
    )
    (net (code "25") (name "Net-(D6-PadC)") (class "Default")
      (node (ref "D6") (pin "C") (pinfunction "C_C") (pintype "passive"))
      (node (ref "R10") (pin "1") (pinfunction "1_1") (pintype "passive"))
    )
    (net (code "26") (name "Net-(DBG1-PadA)") (class "Default")
      (node (ref "DBG1") (pin "A") (pinfunction "A_A") (pintype "passive"))
      (node (ref "R11") (pin "1") (pinfunction "1_1") (pintype "passive"))
    )
    (net (code "27") (name "Net-(DBG2-PadA)") (class "Default")
      (node (ref "DBG2") (pin "A") (pinfunction "A_A") (pintype "passive"))
      (node (ref "R19") (pin "1") (pinfunction "1_1") (pintype "passive"))
    )
    (net (code "28") (name "Net-(DBG3-PadA)") (class "Default")
      (node (ref "DBG3") (pin "A") (pinfunction "A_A") (pintype "passive"))
      (node (ref "R29") (pin "1") (pinfunction "1_1") (pintype "passive"))
    )
    (net (code "29") (name "Net-(DBG4-PadA)") (class "Default")
      (node (ref "DBG4") (pin "A") (pinfunction "A_A") (pintype "passive"))
      (node (ref "R30") (pin "1") (pinfunction "1_1") (pintype "passive"))
    )
    (net (code "30") (name "Net-(F2-Pad1)") (class "Default")
      (node (ref "F2") (pin "1") (pinfunction "1_1") (pintype "passive"))
      (node (ref "USB") (pin "VBUS") (pinfunction "VBUS_VBUS") (pintype "bidirectional"))
    )
    (net (code "31") (name "Net-(IC1-VO)") (class "Default")
      (node (ref "F1") (pin "2") (pinfunction "2_2") (pintype "passive"))
      (node (ref "IC1") (pin "2") (pinfunction "VO_2") (pintype "passive"))
    )
    (net (code "32") (name "Net-(IC2-PB6(XTAL1{slash}TOSC1{slash}PCINT6))") (class "Default")
      (node (ref "IC2") (pin "7") (pinfunction "PB6(XTAL1/TOSC1/PCINT6)_7") (pintype "bidirectional"))
      (node (ref "X4") (pin "1") (pinfunction "1_1") (pintype "passive"))
    )
    (net (code "33") (name "Net-(IC2-PB7(XTAL2{slash}TOSC2{slash}PCINT7))") (class "Default")
      (node (ref "IC2") (pin "8") (pinfunction "PB7(XTAL2/TOSC2/PCINT7)_8") (pintype "bidirectional"))
      (node (ref "X4") (pin "3") (pinfunction "3_3") (pintype "passive"))
    )
    (net (code "34") (name "Net-(IC2-PC0(ADC0{slash}PCINT8))") (class "Default")
      (node (ref "IC2") (pin "23") (pinfunction "PC0(ADC0/PCINT8)_23") (pintype "bidirectional"))
      (node (ref "R11") (pin "2") (pinfunction "2_2") (pintype "passive"))
    )
    (net (code "35") (name "Net-(IC2-PC1(ADC1{slash}PCINT9))") (class "Default")
      (node (ref "IC2") (pin "24") (pinfunction "PC1(ADC1/PCINT9)_24") (pintype "bidirectional"))
      (node (ref "R19") (pin "2") (pinfunction "2_2") (pintype "passive"))
    )
    (net (code "36") (name "Net-(IC2-PC2(ADC2{slash}PCINT10))") (class "Default")
      (node (ref "IC2") (pin "25") (pinfunction "PC2(ADC2/PCINT10)_25") (pintype "bidirectional"))
      (node (ref "R29") (pin "2") (pinfunction "2_2") (pintype "passive"))
    )
    (net (code "37") (name "Net-(IC2-PC3(ADC3{slash}PCINT11))") (class "Default")
      (node (ref "IC2") (pin "26") (pinfunction "PC3(ADC3/PCINT11)_26") (pintype "bidirectional"))
      (node (ref "R30") (pin "2") (pinfunction "2_2") (pintype "passive"))
    )
    (net (code "38") (name "Net-(IC3-CBUS0)") (class "Default")
      (node (ref "IC3") (pin "23") (pinfunction "CBUS0_23") (pintype "bidirectional"))
      (node (ref "R25") (pin "1") (pinfunction "1_1") (pintype "passive"))
    )
    (net (code "39") (name "Net-(IC3-CBUS1)") (class "Default")
      (node (ref "IC3") (pin "22") (pinfunction "CBUS1_22") (pintype "bidirectional"))
      (node (ref "R26") (pin "1") (pinfunction "1_1") (pintype "passive"))
    )
    (net (code "40") (name "Net-(IC3-RXD)") (class "Default")
      (node (ref "IC3") (pin "5") (pinfunction "RXD_5") (pintype "input"))
      (node (ref "R23") (pin "2") (pinfunction "2_2") (pintype "passive"))
    )
    (net (code "41") (name "Net-(IC3-TXD)") (class "Default")
      (node (ref "IC3") (pin "1") (pinfunction "TXD_1") (pintype "output"))
      (node (ref "R24") (pin "2") (pinfunction "2_2") (pintype "passive"))
    )
    (net (code "42") (name "Net-(IC3-~{DTR})") (class "Default")
      (node (ref "C18") (pin "1") (pinfunction "1_1") (pintype "passive"))
      (node (ref "IC3") (pin "2") (pinfunction "~{DTR}_2") (pintype "output"))
    )
    (net (code "43") (name "Net-(IC4-P$1)") (class "Default")
      (node (ref "IC4") (pin "1") (pinfunction "P$1_1") (pintype "bidirectional"))
      (node (ref "R15") (pin "1") (pinfunction "1_1") (pintype "passive"))
    )
    (net (code "44") (name "Net-(IC4-P$2)") (class "Default")
      (node (ref "IC4") (pin "2") (pinfunction "P$2_2") (pintype "bidirectional"))
      (node (ref "LED2") (pin "1") (pinfunction "1_1") (pintype "passive"))
      (node (ref "T1") (pin "3") (pinfunction "C_3") (pintype "passive"))
    )
    (net (code "45") (name "Net-(IC4-P$3)") (class "Default")
      (node (ref "IC4") (pin "3") (pinfunction "P$3_3") (pintype "bidirectional"))
      (node (ref "Q3") (pin "3") (pinfunction "S_3") (pintype "passive"))
      (node (ref "Q4") (pin "3") (pinfunction "S_3") (pintype "passive"))
    )
    (net (code "46") (name "Net-(IC4-P$4)") (class "Default")
      (node (ref "IC4") (pin "4") (pinfunction "P$4_4") (pintype "bidirectional"))
      (node (ref "R14") (pin "2") (pinfunction "2_2") (pintype "passive"))
    )
    (net (code "47") (name "Net-(IC5-P$1)") (class "Default")
      (node (ref "IC5") (pin "1") (pinfunction "P$1_1") (pintype "bidirectional"))
      (node (ref "R2") (pin "1") (pinfunction "1_1") (pintype "passive"))
    )
    (net (code "48") (name "Net-(IC5-P$2)") (class "Default")
      (node (ref "IC5") (pin "2") (pinfunction "P$2_2") (pintype "bidirectional"))
      (node (ref "LED1") (pin "1") (pinfunction "1_1") (pintype "passive"))
      (node (ref "T2") (pin "3") (pinfunction "C_3") (pintype "passive"))
    )
    (net (code "49") (name "Net-(IC5-P$3)") (class "Default")
      (node (ref "IC5") (pin "3") (pinfunction "P$3_3") (pintype "bidirectional"))
      (node (ref "Q1") (pin "3") (pinfunction "S_3") (pintype "passive"))
      (node (ref "Q2") (pin "3") (pinfunction "S_3") (pintype "passive"))
    )
    (net (code "50") (name "Net-(IC5-P$4)") (class "Default")
      (node (ref "IC5") (pin "4") (pinfunction "P$4_4") (pintype "bidirectional"))
      (node (ref "R1") (pin "2") (pinfunction "2_2") (pintype "passive"))
    )
    (net (code "51") (name "Net-(LED1-Pad2)") (class "Default")
      (node (ref "LED1") (pin "2") (pinfunction "2_2") (pintype "passive"))
      (node (ref "R3") (pin "1") (pinfunction "1_1") (pintype "passive"))
    )
    (net (code "52") (name "Net-(LED2-Pad2)") (class "Default")
      (node (ref "LED2") (pin "2") (pinfunction "2_2") (pintype "passive"))
      (node (ref "R16") (pin "1") (pinfunction "1_1") (pintype "passive"))
    )
    (net (code "53") (name "Net-(LM2940SX-12-VIN)") (class "Default")
      (node (ref "F4") (pin "1") (pinfunction "1_1") (pintype "passive"))
      (node (ref "LM2940SX-12") (pin "1") (pinfunction "VIN_1") (pintype "power_in"))
    )
    (net (code "54") (name "Net-(OK1-AC1)") (class "Default")
      (node (ref "OK1") (pin "1") (pinfunction "AC1_1") (pintype "passive"))
      (node (ref "R10") (pin "2") (pinfunction "2_2") (pintype "passive"))
    )
    (net (code "55") (name "Net-(Q1-G)") (class "Default")
      (node (ref "Q1") (pin "1") (pinfunction "G_1") (pintype "passive"))
      (node (ref "Q2") (pin "1") (pinfunction "G_1") (pintype "passive"))
      (node (ref "R1") (pin "1") (pinfunction "1_1") (pintype "passive"))
    )
    (net (code "56") (name "Net-(Q2-D)") (class "Default")
      (node (ref "Q2") (pin "2") (pinfunction "D_2") (pintype "passive"))
      (node (ref "X2") (pin "3") (pinfunction "KL_3") (pintype "passive"))
    )
    (net (code "57") (name "Net-(Q3-G)") (class "Default")
      (node (ref "Q3") (pin "1") (pinfunction "G_1") (pintype "passive"))
      (node (ref "Q4") (pin "1") (pinfunction "G_1") (pintype "passive"))
      (node (ref "R14") (pin "1") (pinfunction "1_1") (pintype "passive"))
    )
    (net (code "58") (name "Net-(Q4-D)") (class "Default")
      (node (ref "Q4") (pin "2") (pinfunction "D_2") (pintype "passive"))
      (node (ref "X3") (pin "3") (pinfunction "KL_3") (pintype "passive"))
    )
    (net (code "59") (name "Net-(R13-2)") (class "Default")
      (node (ref "D1") (pin "A") (pinfunction "A_A") (pintype "passive"))
      (node (ref "D6") (pin "A") (pinfunction "A_A") (pintype "passive"))
      (node (ref "R13") (pin "P$2") (pinfunction "2_P$2") (pintype "passive"))
    )
    (net (code "60") (name "Net-(R25-Pad2)") (class "Default")
      (node (ref "R25") (pin "2") (pinfunction "2_2") (pintype "passive"))
      (node (ref "RX") (pin "C") (pinfunction "C_C") (pintype "passive"))
    )
    (net (code "61") (name "Net-(R26-Pad2)") (class "Default")
      (node (ref "R26") (pin "2") (pinfunction "2_2") (pintype "passive"))
      (node (ref "TX") (pin "C") (pinfunction "C_C") (pintype "passive"))
    )
    (net (code "62") (name "Net-(R27-Pad2)") (class "Default")
      (node (ref "R27") (pin "2") (pinfunction "2_2") (pintype "passive"))
      (node (ref "TEMP1") (pin "2") (pinfunction "2_2") (pintype "passive"))
    )
    (net (code "63") (name "Net-(R28-Pad1)") (class "Default")
      (node (ref "R28") (pin "1") (pinfunction "1_1") (pintype "passive"))
      (node (ref "R31") (pin "2") (pinfunction "2_2") (pintype "passive"))
      (node (ref "SG2") (pin "-") (pinfunction "-_-") (pintype "passive"))
    )
    (net (code "64") (name "Net-(R32-Pad2)") (class "Default")
      (node (ref "R32") (pin "2") (pinfunction "2_2") (pintype "passive"))
      (node (ref "TEMP2") (pin "2") (pinfunction "2_2") (pintype "passive"))
    )
    (net (code "65") (name "Net-(T3-C)") (class "Default")
      (node (ref "R31") (pin "1") (pinfunction "1_1") (pintype "passive"))
      (node (ref "T3") (pin "3") (pinfunction "C_3") (pintype "passive"))
    )
    (net (code "66") (name "Net-(X1B-KL)") (class "Default")
      (node (ref "F3") (pin "1") (pinfunction "1_1") (pintype "passive"))
      (node (ref "X1") (pin "2") (pinfunction "KL_2") (pintype "passive"))
    )
    (net (code "67") (name "Net-(X2A-KL)") (class "Default")
      (node (ref "R18") (pin "1") (pinfunction "1_1") (pintype "passive"))
      (node (ref "R9") (pin "2") (pinfunction "2_2") (pintype "passive"))
      (node (ref "X2") (pin "1") (pinfunction "KL_1") (pintype "passive"))
    )
    (net (code "68") (name "Net-(X3A-KL)") (class "Default")
      (node (ref "R17") (pin "1") (pinfunction "1_1") (pintype "passive"))
      (node (ref "R8") (pin "2") (pinfunction "2_2") (pintype "passive"))
      (node (ref "X3") (pin "1") (pinfunction "KL_1") (pintype "passive"))
    )
    (net (code "69") (name "OLED_CS") (class "Default")
      (node (ref "IC2") (pin "2") (pinfunction "PD4(T0/XCK/PCINT20)_2") (pintype "bidirectional"))
      (node (ref "OLED2") (pin "3") (pinfunction "3_3") (pintype "passive"))
    )
    (net (code "70") (name "OLED_DC") (class "Default")
      (node (ref "IC2") (pin "11") (pinfunction "PD7(AIN1/PCINT23)_11") (pintype "bidirectional"))
      (node (ref "OLED2") (pin "4") (pinfunction "4_4") (pintype "passive"))
    )
    (net (code "71") (name "RESET") (class "Default")
      (node (ref "IC2") (pin "29") (pinfunction "PC6(/RESET/PCINT14)_29") (pintype "bidirectional"))
      (node (ref "JP1") (pin "2") (pinfunction "2_2") (pintype "passive"))
      (node (ref "JP2") (pin "3") (pinfunction "3_3") (pintype "passive"))
      (node (ref "R20") (pin "1") (pinfunction "1_1") (pintype "passive"))
      (node (ref "RESET") (pin "P$3") (pinfunction "2_P$3") (pintype "passive"))
      (node (ref "RESET") (pin "P$4") (pinfunction "2_P$4") (pintype "passive"))
      (node (ref "U$5") (pin "RST") (pinfunction "P$3_RST") (pintype "bidirectional"))
    )
    (net (code "72") (name "RX") (class "Default")
      (node (ref "IC2") (pin "30") (pinfunction "PD0(RXD/PCINT16)_30") (pintype "bidirectional"))
      (node (ref "R24") (pin "1") (pinfunction "1_1") (pintype "passive"))
    )
    (net (code "73") (name "SCK") (class "Default")
      (node (ref "IC2") (pin "17") (pinfunction "PB5(SCK/PCINT5)_17") (pintype "bidirectional"))
      (node (ref "OLED2") (pin "1") (pinfunction "1_1") (pintype "passive"))
      (node (ref "U$5") (pin "SCK") (pinfunction "P$2_SCK") (pintype "bidirectional"))
    )
    (net (code "74") (name "SCL_MC") (class "Default")
      (node (ref "I2C2") (pin "2") (pinfunction "2_2") (pintype "passive"))
      (node (ref "IC2") (pin "28") (pinfunction "PC5(ADC5/SCL/PCINT13)_28") (pintype "bidirectional"))
    )
    (net (code "75") (name "SCL_PWR") (class "Default")
      (node (ref "I2C1") (pin "2") (pinfunction "2_2") (pintype "passive"))
      (node (ref "R7") (pin "1") (pinfunction "1_1") (pintype "passive"))
      (node (ref "U1") (pin "10") (pinfunction "SCL_10") (pintype "bidirectional"))
      (node (ref "U2") (pin "4") (pinfunction "SCL_4") (pintype "input"))
    )
    (net (code "76") (name "SDA_MC") (class "Default")
      (node (ref "I2C2") (pin "3") (pinfunction "3_3") (pintype "passive"))
      (node (ref "IC2") (pin "27") (pinfunction "PC4(ADC4/SDA/PCINT12)_27") (pintype "bidirectional"))
    )
    (net (code "77") (name "SDA_PWR") (class "Default")
      (node (ref "I2C1") (pin "3") (pinfunction "3_3") (pintype "passive"))
      (node (ref "R6") (pin "1") (pinfunction "1_1") (pintype "passive"))
      (node (ref "U1") (pin "9") (pinfunction "SDA_9") (pintype "bidirectional"))
      (node (ref "U2") (pin "6") (pinfunction "SDA_6") (pintype "bidirectional"))
    )
    (net (code "78") (name "TC_1_N") (class "Default")
      (node (ref "C5") (pin "2") (pinfunction "2_2") (pintype "passive"))
      (node (ref "D9") (pin "1") (pinfunction "A1_1") (pintype "passive"))
      (node (ref "D9") (pin "2") (pinfunction "C2_2") (pintype "passive"))
      (node (ref "R9") (pin "1") (pinfunction "1_1") (pintype "passive"))
      (node (ref "U$2") (pin "P$1") (pinfunction "P$1_P$1") (pintype "bidirectional"))
      (node (ref "U1") (pin "5") (pinfunction "AIN1_5") (pintype "bidirectional"))
    )
    (net (code "79") (name "TC_1_P") (class "Default")
      (node (ref "C5") (pin "1") (pinfunction "1_1") (pintype "passive"))
      (node (ref "D9") (pin "3") (pinfunction "C1A2_3") (pintype "passive"))
      (node (ref "R18") (pin "2") (pinfunction "2_2") (pintype "passive"))
      (node (ref "U1") (pin "4") (pinfunction "AIN0_4") (pintype "bidirectional"))
    )
    (net (code "80") (name "TC_2_N") (class "Default")
      (node (ref "C4") (pin "2") (pinfunction "2_2") (pintype "passive"))
      (node (ref "D8") (pin "1") (pinfunction "A1_1") (pintype "passive"))
      (node (ref "D8") (pin "2") (pinfunction "C2_2") (pintype "passive"))
      (node (ref "R8") (pin "1") (pinfunction "1_1") (pintype "passive"))
      (node (ref "U$3") (pin "P$1") (pinfunction "P$1_P$1") (pintype "bidirectional"))
      (node (ref "U1") (pin "7") (pinfunction "AIN3_7") (pintype "bidirectional"))
    )
    (net (code "81") (name "TC_2_P") (class "Default")
      (node (ref "C4") (pin "1") (pinfunction "1_1") (pintype "passive"))
      (node (ref "D8") (pin "3") (pinfunction "C1A2_3") (pintype "passive"))
      (node (ref "R17") (pin "2") (pinfunction "2_2") (pintype "passive"))
      (node (ref "U1") (pin "6") (pinfunction "AIN2_6") (pintype "bidirectional"))
    )
    (net (code "82") (name "TX") (class "Default")
      (node (ref "IC2") (pin "31") (pinfunction "PD1(TXD/PCINT17)_31") (pintype "bidirectional"))
      (node (ref "R23") (pin "1") (pinfunction "1_1") (pintype "passive"))
    )
    (net (code "83") (name "USB+") (class "Default")
      (node (ref "IC3") (pin "15") (pinfunction "USBDP_15") (pintype "bidirectional"))
      (node (ref "USB") (pin "D+") (pinfunction "D+_D+") (pintype "bidirectional"))
    )
    (net (code "84") (name "USB-") (class "Default")
      (node (ref "IC3") (pin "16") (pinfunction "USBDM_16") (pintype "bidirectional"))
      (node (ref "USB") (pin "D-") (pinfunction "D-_D-") (pintype "bidirectional"))
    )
    (net (code "85") (name "V_USB") (class "Default")
      (node (ref "C21") (pin "1") (pinfunction "1_1") (pintype "passive"))
      (node (ref "C22") (pin "1") (pinfunction "1_1") (pintype "passive"))
      (node (ref "D2") (pin "A") (pinfunction "A_A") (pintype "passive"))
      (node (ref "F2") (pin "2") (pinfunction "2_2") (pintype "passive"))
    )
    (net (code "86") (name "ZC_MC") (class "Default")
      (node (ref "IC2") (pin "32") (pinfunction "PD2(INT0/PCINT18)_32") (pintype "bidirectional"))
      (node (ref "SIG2") (pin "2") (pinfunction "2_2") (pintype "passive"))
    )
    (net (code "87") (name "ZC_PWR") (class "Default")
      (node (ref "OK1") (pin "4") (pinfunction "C_4") (pintype "passive"))
      (node (ref "R12") (pin "2") (pinfunction "2_2") (pintype "passive"))
      (node (ref "SIG1") (pin "2") (pinfunction "2_2") (pintype "passive"))
    )
    (net (code "88") (name "unconnected-(IC3-CBUS2-Pad13)") (class "Default")
      (node (ref "IC3") (pin "13") (pinfunction "CBUS2_13") (pintype "bidirectional"))
    )
    (net (code "89") (name "unconnected-(IC3-CBUS3-Pad14)") (class "Default")
      (node (ref "IC3") (pin "14") (pinfunction "CBUS3_14") (pintype "bidirectional"))
    )
    (net (code "90") (name "unconnected-(IC3-CBUS4-Pad12)") (class "Default")
      (node (ref "IC3") (pin "12") (pinfunction "CBUS4_12") (pintype "bidirectional"))
    )
    (net (code "91") (name "unconnected-(IC3-OSCI-Pad27)") (class "Default")
      (node (ref "IC3") (pin "27") (pinfunction "OSCI_27") (pintype "input"))
    )
    (net (code "92") (name "unconnected-(IC3-OSCO-Pad28)") (class "Default")
      (node (ref "IC3") (pin "28") (pinfunction "OSCO_28") (pintype "output"))
    )
    (net (code "93") (name "unconnected-(IC3-~{CTS}-Pad11)") (class "Default")
      (node (ref "IC3") (pin "11") (pinfunction "~{CTS}_11") (pintype "input"))
    )
    (net (code "94") (name "unconnected-(IC3-~{DCD}-Pad10)") (class "Default")
      (node (ref "IC3") (pin "10") (pinfunction "~{DCD}_10") (pintype "input"))
    )
    (net (code "95") (name "unconnected-(IC3-~{DSR}-Pad9)") (class "Default")
      (node (ref "IC3") (pin "9") (pinfunction "~{DSR}_9") (pintype "input"))
    )
    (net (code "96") (name "unconnected-(IC3-~{RESET}-Pad19)") (class "Default")
      (node (ref "IC3") (pin "19") (pinfunction "~{RESET}_19") (pintype "input"))
    )
    (net (code "97") (name "unconnected-(IC3-~{RI}-Pad6)") (class "Default")
      (node (ref "IC3") (pin "6") (pinfunction "~{RI}_6") (pintype "input"))
    )
    (net (code "98") (name "unconnected-(IC3-~{RTS}-Pad3)") (class "Default")
      (node (ref "IC3") (pin "3") (pinfunction "~{RTS}_3") (pintype "output"))
    )
    (net (code "99") (name "unconnected-(JP2-Pad1)") (class "Default")
      (node (ref "JP2") (pin "1") (pinfunction "1_1") (pintype "passive"))
    )
    (net (code "100") (name "unconnected-(U2-ADDR-Pad1)") (class "Default")
      (node (ref "U2") (pin "1") (pinfunction "ADDR_1") (pintype "input"))
    )
    (net (code "101") (name "unconnected-(USB-PadID)") (class "Default")
      (node (ref "USB") (pin "ID") (pinfunction "ID_ID") (pintype "bidirectional"))
    )
  )
)
